# chromatic_drum_gate_sync_v001.net
KiCad netlist of a schematic drawn in EAGLE
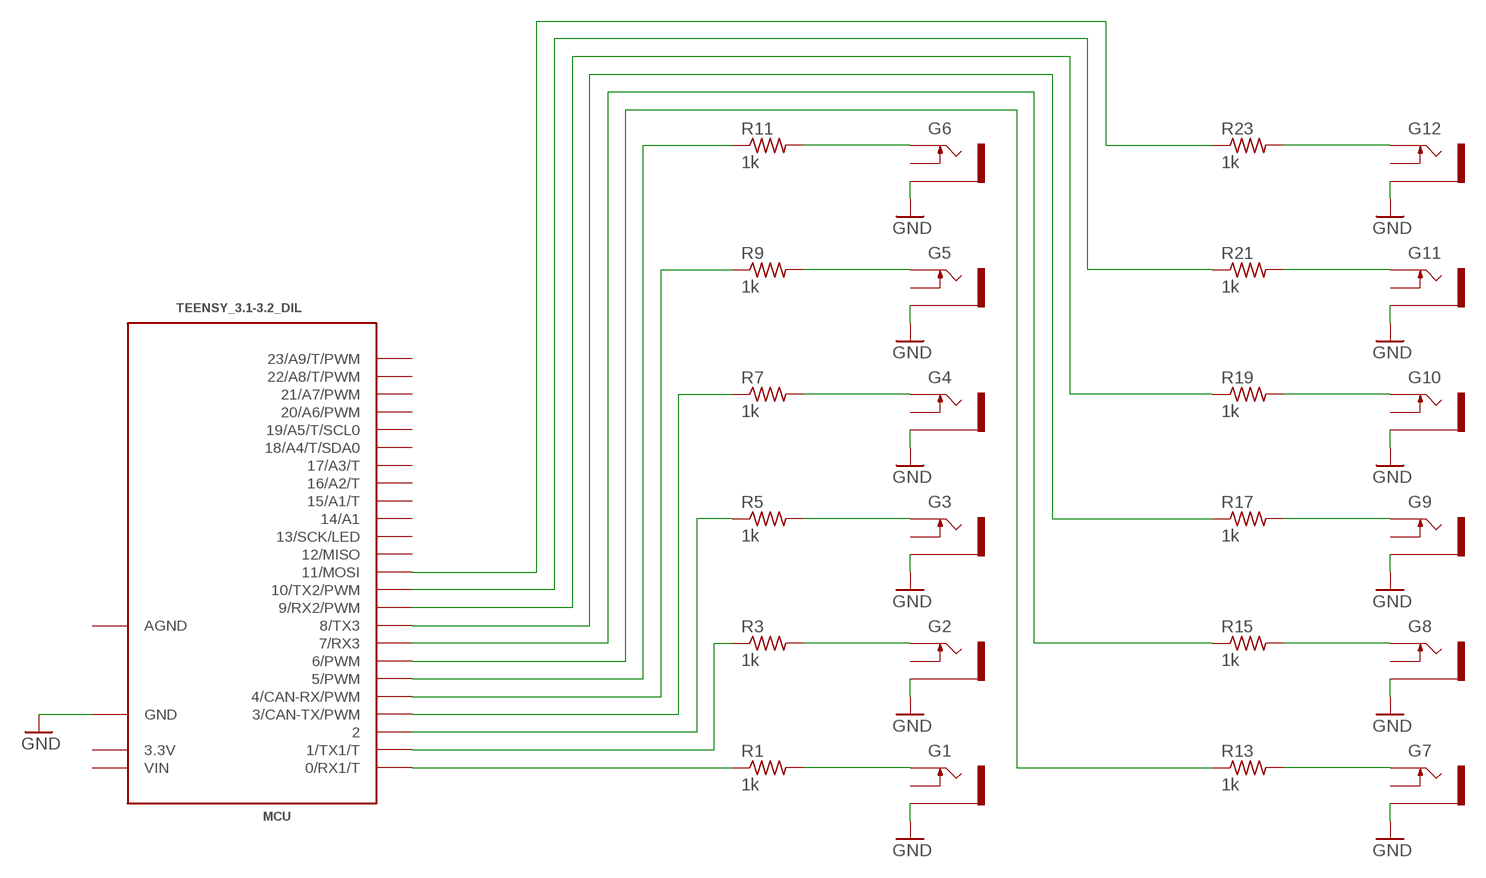
[diagram p0: schematic, sheet 1]

(export (version "E")
  (design (tool "Eeschema 10.0.6"))
  (components
    (comp (ref "G1")
      (value "THONKICONNNEW")
      (footprint "eagle-import:WQP-PJ301M-12_JACK")
      (libsource (lib "eagle-import") (part "THONKICONNNEW"))
    )
    (comp (ref "G2")
      (value "THONKICONNNEW")
      (footprint "eagle-import:WQP-PJ301M-12_JACK")
      (libsource (lib "eagle-import") (part "THONKICONNNEW"))
    )
    (comp (ref "G3")
      (value "THONKICONNNEW")
      (footprint "eagle-import:WQP-PJ301M-12_JACK")
      (libsource (lib "eagle-import") (part "THONKICONNNEW"))
    )
    (comp (ref "G4")
      (value "THONKICONNNEW")
      (footprint "eagle-import:WQP-PJ301M-12_JACK")
      (libsource (lib "eagle-import") (part "THONKICONNNEW"))
    )
    (comp (ref "G5")
      (value "THONKICONNNEW")
      (footprint "eagle-import:WQP-PJ301M-12_JACK")
      (libsource (lib "eagle-import") (part "THONKICONNNEW"))
    )
    (comp (ref "G6")
      (value "THONKICONNNEW")
      (footprint "eagle-import:WQP-PJ301M-12_JACK")
      (libsource (lib "eagle-import") (part "THONKICONNNEW"))
    )
    (comp (ref "G7")
      (value "THONKICONNNEW")
      (footprint "eagle-import:WQP-PJ301M-12_JACK")
      (libsource (lib "eagle-import") (part "THONKICONNNEW"))
    )
    (comp (ref "G8")
      (value "THONKICONNNEW")
      (footprint "eagle-import:WQP-PJ301M-12_JACK")
      (libsource (lib "eagle-import") (part "THONKICONNNEW"))
    )
    (comp (ref "G9")
      (value "THONKICONNNEW")
      (footprint "eagle-import:WQP-PJ301M-12_JACK")
      (libsource (lib "eagle-import") (part "THONKICONNNEW"))
    )
    (comp (ref "G10")
      (value "THONKICONNNEW")
      (footprint "eagle-import:WQP-PJ301M-12_JACK")
      (libsource (lib "eagle-import") (part "THONKICONNNEW"))
    )
    (comp (ref "G11")
      (value "THONKICONNNEW")
      (footprint "eagle-import:WQP-PJ301M-12_JACK")
      (libsource (lib "eagle-import") (part "THONKICONNNEW"))
    )
    (comp (ref "G12")
      (value "THONKICONNNEW")
      (footprint "eagle-import:WQP-PJ301M-12_JACK")
      (libsource (lib "eagle-import") (part "THONKICONNNEW"))
    )
    (comp (ref "MCU")
      (value "TEENSY_3.1-3.2_DIL")
      (footprint "eagle-import:TEENSY_3.0-3.2&LC_DIL")
      (libsource (lib "eagle-import") (part "TEENSY_3.1-3.2_DIL"))
    )
    (comp (ref "R1")
      (value "1k")
      (footprint "eagle-import:0207_7")
      (libsource (lib "eagle-import") (part "R-US_0207/7"))
    )
    (comp (ref "R3")
      (value "1k")
      (footprint "eagle-import:0207_7")
      (libsource (lib "eagle-import") (part "R-US_0207/7"))
    )
    (comp (ref "R5")
      (value "1k")
      (footprint "eagle-import:0207_7")
      (libsource (lib "eagle-import") (part "R-US_0207/7"))
    )
    (comp (ref "R7")
      (value "1k")
      (footprint "eagle-import:0207_7")
      (libsource (lib "eagle-import") (part "R-US_0207/7"))
    )
    (comp (ref "R9")
      (value "1k")
      (footprint "eagle-import:0207_7")
      (libsource (lib "eagle-import") (part "R-US_0207/7"))
    )
    (comp (ref "R11")
      (value "1k")
      (footprint "eagle-import:0207_7")
      (libsource (lib "eagle-import") (part "R-US_0207/7"))
    )
    (comp (ref "R13")
      (value "1k")
      (footprint "eagle-import:0207_7")
      (libsource (lib "eagle-import") (part "R-US_0207/7"))
    )
    (comp (ref "R15")
      (value "1k")
      (footprint "eagle-import:0207_7")
      (libsource (lib "eagle-import") (part "R-US_0207/7"))
    )
    (comp (ref "R17")
      (value "1k")
      (footprint "eagle-import:0207_7")
      (libsource (lib "eagle-import") (part "R-US_0207/7"))
    )
    (comp (ref "R19")
      (value "1k")
      (footprint "eagle-import:0207_7")
      (libsource (lib "eagle-import") (part "R-US_0207/7"))
    )
    (comp (ref "R21")
      (value "1k")
      (footprint "eagle-import:0207_7")
      (libsource (lib "eagle-import") (part "R-US_0207/7"))
    )
    (comp (ref "R23")
      (value "1k")
      (footprint "eagle-import:0207_7")
      (libsource (lib "eagle-import") (part "R-US_0207/7"))
    )
  )
  (nets
    (net (code "1") (name "/3.3V") (class "Default")
      (node (ref "MCU") (pin "3.3V") (pinfunction "3.3V_3.3V") (pintype "power_in"))
    )
    (net (code "2") (name "/AGND") (class "Default")
      (node (ref "MCU") (pin "AGND") (pinfunction "AGND_AGND") (pintype "power_in"))
    )
    (net (code "3") (name "/VIN") (class "Default")
      (node (ref "MCU") (pin "VIN") (pinfunction "VIN_VIN") (pintype "power_in"))
    )
    (net (code "4") (name "GND") (class "Default")
      (node (ref "G1") (pin "P$3_SLEEVE") (pinfunction "SLEEVE_P$3_SLEEVE") (pintype "passive"))
      (node (ref "G10") (pin "P$3_SLEEVE") (pinfunction "SLEEVE_P$3_SLEEVE") (pintype "passive"))
      (node (ref "G11") (pin "P$3_SLEEVE") (pinfunction "SLEEVE_P$3_SLEEVE") (pintype "passive"))
      (node (ref "G12") (pin "P$3_SLEEVE") (pinfunction "SLEEVE_P$3_SLEEVE") (pintype "passive"))
      (node (ref "G2") (pin "P$3_SLEEVE") (pinfunction "SLEEVE_P$3_SLEEVE") (pintype "passive"))
      (node (ref "G3") (pin "P$3_SLEEVE") (pinfunction "SLEEVE_P$3_SLEEVE") (pintype "passive"))
      (node (ref "G4") (pin "P$3_SLEEVE") (pinfunction "SLEEVE_P$3_SLEEVE") (pintype "passive"))
      (node (ref "G5") (pin "P$3_SLEEVE") (pinfunction "SLEEVE_P$3_SLEEVE") (pintype "passive"))
      (node (ref "G6") (pin "P$3_SLEEVE") (pinfunction "SLEEVE_P$3_SLEEVE") (pintype "passive"))
      (node (ref "G7") (pin "P$3_SLEEVE") (pinfunction "SLEEVE_P$3_SLEEVE") (pintype "passive"))
      (node (ref "G8") (pin "P$3_SLEEVE") (pinfunction "SLEEVE_P$3_SLEEVE") (pintype "passive"))
      (node (ref "G9") (pin "P$3_SLEEVE") (pinfunction "SLEEVE_P$3_SLEEVE") (pintype "passive"))
      (node (ref "MCU") (pin "GND") (pinfunction "GND_GND") (pintype "power_in"))
    )
    (net (code "5") (name "Net-(G1-TIP)") (class "Default")
      (node (ref "G1") (pin "P$1_TIP") (pinfunction "TIP_P$1_TIP") (pintype "passive"))
      (node (ref "R1") (pin "2") (pinfunction "2_2") (pintype "passive"))
    )
    (net (code "6") (name "Net-(G2-TIP)") (class "Default")
      (node (ref "G2") (pin "P$1_TIP") (pinfunction "TIP_P$1_TIP") (pintype "passive"))
      (node (ref "R3") (pin "2") (pinfunction "2_2") (pintype "passive"))
    )
    (net (code "7") (name "Net-(G3-TIP)") (class "Default")
      (node (ref "G3") (pin "P$1_TIP") (pinfunction "TIP_P$1_TIP") (pintype "passive"))
      (node (ref "R5") (pin "2") (pinfunction "2_2") (pintype "passive"))
    )
    (net (code "8") (name "Net-(G4-TIP)") (class "Default")
      (node (ref "G4") (pin "P$1_TIP") (pinfunction "TIP_P$1_TIP") (pintype "passive"))
      (node (ref "R7") (pin "2") (pinfunction "2_2") (pintype "passive"))
    )
    (net (code "9") (name "Net-(G5-TIP)") (class "Default")
      (node (ref "G5") (pin "P$1_TIP") (pinfunction "TIP_P$1_TIP") (pintype "passive"))
      (node (ref "R9") (pin "2") (pinfunction "2_2") (pintype "passive"))
    )
    (net (code "10") (name "Net-(G6-TIP)") (class "Default")
      (node (ref "G6") (pin "P$1_TIP") (pinfunction "TIP_P$1_TIP") (pintype "passive"))
      (node (ref "R11") (pin "2") (pinfunction "2_2") (pintype "passive"))
    )
    (net (code "11") (name "Net-(G7-TIP)") (class "Default")
      (node (ref "G7") (pin "P$1_TIP") (pinfunction "TIP_P$1_TIP") (pintype "passive"))
      (node (ref "R13") (pin "2") (pinfunction "2_2") (pintype "passive"))
    )
    (net (code "12") (name "Net-(G8-TIP)") (class "Default")
      (node (ref "G8") (pin "P$1_TIP") (pinfunction "TIP_P$1_TIP") (pintype "passive"))
      (node (ref "R15") (pin "2") (pinfunction "2_2") (pintype "passive"))
    )
    (net (code "13") (name "Net-(G9-TIP)") (class "Default")
      (node (ref "G9") (pin "P$1_TIP") (pinfunction "TIP_P$1_TIP") (pintype "passive"))
      (node (ref "R17") (pin "2") (pinfunction "2_2") (pintype "passive"))
    )
    (net (code "14") (name "Net-(G10-TIP)") (class "Default")
      (node (ref "G10") (pin "P$1_TIP") (pinfunction "TIP_P$1_TIP") (pintype "passive"))
      (node (ref "R19") (pin "2") (pinfunction "2_2") (pintype "passive"))
    )
    (net (code "15") (name "Net-(G11-TIP)") (class "Default")
      (node (ref "G11") (pin "P$1_TIP") (pinfunction "TIP_P$1_TIP") (pintype "passive"))
      (node (ref "R21") (pin "2") (pinfunction "2_2") (pintype "passive"))
    )
    (net (code "16") (name "Net-(G12-TIP)") (class "Default")
      (node (ref "G12") (pin "P$1_TIP") (pinfunction "TIP_P$1_TIP") (pintype "passive"))
      (node (ref "R23") (pin "2") (pinfunction "2_2") (pintype "passive"))
    )
    (net (code "17") (name "Net-(MCU-0{slash}RX1{slash}T)") (class "Default")
      (node (ref "MCU") (pin "0") (pinfunction "0/RX1/T_0") (pintype "bidirectional"))
      (node (ref "R1") (pin "1") (pinfunction "1_1") (pintype "passive"))
    )
    (net (code "18") (name "Net-(MCU-1{slash}TX1{slash}T)") (class "Default")
      (node (ref "MCU") (pin "1") (pinfunction "1/TX1/T_1") (pintype "bidirectional"))
      (node (ref "R3") (pin "1") (pinfunction "1_1") (pintype "passive"))
    )
    (net (code "19") (name "Net-(MCU-3{slash}CAN-TX{slash}PWM)") (class "Default")
      (node (ref "MCU") (pin "3") (pinfunction "3/CAN-TX/PWM_3") (pintype "bidirectional"))
      (node (ref "R7") (pin "1") (pinfunction "1_1") (pintype "passive"))
    )
    (net (code "20") (name "Net-(MCU-4{slash}CAN-RX{slash}PWM)") (class "Default")
      (node (ref "MCU") (pin "4") (pinfunction "4/CAN-RX/PWM_4") (pintype "bidirectional"))
      (node (ref "R9") (pin "1") (pinfunction "1_1") (pintype "passive"))
    )
    (net (code "21") (name "Net-(MCU-5{slash}PWM)") (class "Default")
      (node (ref "MCU") (pin "5") (pinfunction "5/PWM_5") (pintype "bidirectional"))
      (node (ref "R11") (pin "1") (pinfunction "1_1") (pintype "passive"))
    )
    (net (code "22") (name "Net-(MCU-6{slash}PWM)") (class "Default")
      (node (ref "MCU") (pin "6") (pinfunction "6/PWM_6") (pintype "bidirectional"))
      (node (ref "R13") (pin "1") (pinfunction "1_1") (pintype "passive"))
    )
    (net (code "23") (name "Net-(MCU-7{slash}RX3)") (class "Default")
      (node (ref "MCU") (pin "7") (pinfunction "7/RX3_7") (pintype "bidirectional"))
      (node (ref "R15") (pin "1") (pinfunction "1_1") (pintype "passive"))
    )
    (net (code "24") (name "Net-(MCU-8{slash}TX3)") (class "Default")
      (node (ref "MCU") (pin "8") (pinfunction "8/TX3_8") (pintype "bidirectional"))
      (node (ref "R17") (pin "1") (pinfunction "1_1") (pintype "passive"))
    )
    (net (code "25") (name "Net-(MCU-9{slash}RX2{slash}PWM)") (class "Default")
      (node (ref "MCU") (pin "9") (pinfunction "9/RX2/PWM_9") (pintype "bidirectional"))
      (node (ref "R19") (pin "1") (pinfunction "1_1") (pintype "passive"))
    )
    (net (code "26") (name "Net-(MCU-10{slash}TX2{slash}PWM)") (class "Default")
      (node (ref "MCU") (pin "10") (pinfunction "10/TX2/PWM_10") (pintype "bidirectional"))
      (node (ref "R21") (pin "1") (pinfunction "1_1") (pintype "passive"))
    )
    (net (code "27") (name "Net-(MCU-11{slash}MOSI)") (class "Default")
      (node (ref "MCU") (pin "11") (pinfunction "11/MOSI_11") (pintype "bidirectional"))
      (node (ref "R23") (pin "1") (pinfunction "1_1") (pintype "passive"))
    )
    (net (code "28") (name "Net-(MCU-Pad2)") (class "Default")
      (node (ref "MCU") (pin "2") (pinfunction "2_2") (pintype "bidirectional"))
      (node (ref "R5") (pin "1") (pinfunction "1_1") (pintype "passive"))
    )
    (net (code "29") (name "unconnected-(G1-SWITCH-PadP$2_SWITCH)") (class "Default")
      (node (ref "G1") (pin "P$2_SWITCH") (pinfunction "SWITCH_P$2_SWITCH") (pintype "passive"))
    )
    (net (code "30") (name "unconnected-(G2-SWITCH-PadP$2_SWITCH)") (class "Default")
      (node (ref "G2") (pin "P$2_SWITCH") (pinfunction "SWITCH_P$2_SWITCH") (pintype "passive"))
    )
    (net (code "31") (name "unconnected-(G3-SWITCH-PadP$2_SWITCH)") (class "Default")
      (node (ref "G3") (pin "P$2_SWITCH") (pinfunction "SWITCH_P$2_SWITCH") (pintype "passive"))
    )
    (net (code "32") (name "unconnected-(G4-SWITCH-PadP$2_SWITCH)") (class "Default")
      (node (ref "G4") (pin "P$2_SWITCH") (pinfunction "SWITCH_P$2_SWITCH") (pintype "passive"))
    )
    (net (code "33") (name "unconnected-(G5-SWITCH-PadP$2_SWITCH)") (class "Default")
      (node (ref "G5") (pin "P$2_SWITCH") (pinfunction "SWITCH_P$2_SWITCH") (pintype "passive"))
    )
    (net (code "34") (name "unconnected-(G6-SWITCH-PadP$2_SWITCH)") (class "Default")
      (node (ref "G6") (pin "P$2_SWITCH") (pinfunction "SWITCH_P$2_SWITCH") (pintype "passive"))
    )
    (net (code "35") (name "unconnected-(G7-SWITCH-PadP$2_SWITCH)") (class "Default")
      (node (ref "G7") (pin "P$2_SWITCH") (pinfunction "SWITCH_P$2_SWITCH") (pintype "passive"))
    )
    (net (code "36") (name "unconnected-(G8-SWITCH-PadP$2_SWITCH)") (class "Default")
      (node (ref "G8") (pin "P$2_SWITCH") (pinfunction "SWITCH_P$2_SWITCH") (pintype "passive"))
    )
    (net (code "37") (name "unconnected-(G9-SWITCH-PadP$2_SWITCH)") (class "Default")
      (node (ref "G9") (pin "P$2_SWITCH") (pinfunction "SWITCH_P$2_SWITCH") (pintype "passive"))
    )
    (net (code "38") (name "unconnected-(G10-SWITCH-PadP$2_SWITCH)") (class "Default")
      (node (ref "G10") (pin "P$2_SWITCH") (pinfunction "SWITCH_P$2_SWITCH") (pintype "passive"))
    )
    (net (code "39") (name "unconnected-(G11-SWITCH-PadP$2_SWITCH)") (class "Default")
      (node (ref "G11") (pin "P$2_SWITCH") (pinfunction "SWITCH_P$2_SWITCH") (pintype "passive"))
    )
    (net (code "40") (name "unconnected-(G12-SWITCH-PadP$2_SWITCH)") (class "Default")
      (node (ref "G12") (pin "P$2_SWITCH") (pinfunction "SWITCH_P$2_SWITCH") (pintype "passive"))
    )
    (net (code "41") (name "unconnected-(MCU-12{slash}MISO-Pad12)") (class "Default")
      (node (ref "MCU") (pin "12") (pinfunction "12/MISO_12") (pintype "bidirectional"))
    )
    (net (code "42") (name "unconnected-(MCU-13{slash}SCK{slash}LED-Pad13)") (class "Default")
      (node (ref "MCU") (pin "13") (pinfunction "13/SCK/LED_13") (pintype "bidirectional"))
    )
    (net (code "43") (name "unconnected-(MCU-14{slash}A1-Pad14{slash}A0)") (class "Default")
      (node (ref "MCU") (pin "14/A0") (pinfunction "14/A1_14/A0") (pintype "bidirectional"))
    )
    (net (code "44") (name "unconnected-(MCU-15{slash}A1{slash}T-Pad15{slash}A1)") (class "Default")
      (node (ref "MCU") (pin "15/A1") (pinfunction "15/A1/T_15/A1") (pintype "bidirectional"))
    )
    (net (code "45") (name "unconnected-(MCU-16{slash}A2{slash}T-Pad16{slash}A2)") (class "Default")
      (node (ref "MCU") (pin "16/A2") (pinfunction "16/A2/T_16/A2") (pintype "bidirectional"))
    )
    (net (code "46") (name "unconnected-(MCU-17{slash}A3{slash}T-Pad17{slash}A3)") (class "Default")
      (node (ref "MCU") (pin "17/A3") (pinfunction "17/A3/T_17/A3") (pintype "bidirectional"))
    )
    (net (code "47") (name "unconnected-(MCU-18{slash}A4{slash}T{slash}SDA0-Pad18{slash}A4)") (class "Default")
      (node (ref "MCU") (pin "18/A4") (pinfunction "18/A4/T/SDA0_18/A4") (pintype "bidirectional"))
    )
    (net (code "48") (name "unconnected-(MCU-19{slash}A5{slash}T{slash}SCL0-Pad19{slash}A5)") (class "Default")
      (node (ref "MCU") (pin "19/A5") (pinfunction "19/A5/T/SCL0_19/A5") (pintype "bidirectional"))
    )
    (net (code "49") (name "unconnected-(MCU-20{slash}A6{slash}PWM-Pad20{slash}A6)") (class "Default")
      (node (ref "MCU") (pin "20/A6") (pinfunction "20/A6/PWM_20/A6") (pintype "bidirectional"))
    )
    (net (code "50") (name "unconnected-(MCU-21{slash}A7{slash}PWM-Pad21{slash}A7)") (class "Default")
      (node (ref "MCU") (pin "21/A7") (pinfunction "21/A7/PWM_21/A7") (pintype "bidirectional"))
    )
    (net (code "51") (name "unconnected-(MCU-22{slash}A8{slash}T{slash}PWM-Pad22{slash}A8)") (class "Default")
      (node (ref "MCU") (pin "22/A8") (pinfunction "22/A8/T/PWM_22/A8") (pintype "bidirectional"))
    )
    (net (code "52") (name "unconnected-(MCU-23{slash}A9{slash}T{slash}PWM-Pad23{slash}A9)") (class "Default")
      (node (ref "MCU") (pin "23/A9") (pinfunction "23/A9/T/PWM_23/A9") (pintype "bidirectional"))
    )
  )
)
